# extruder-flex-heater.net
KiCad netlist of a schematic drawn in EAGLE
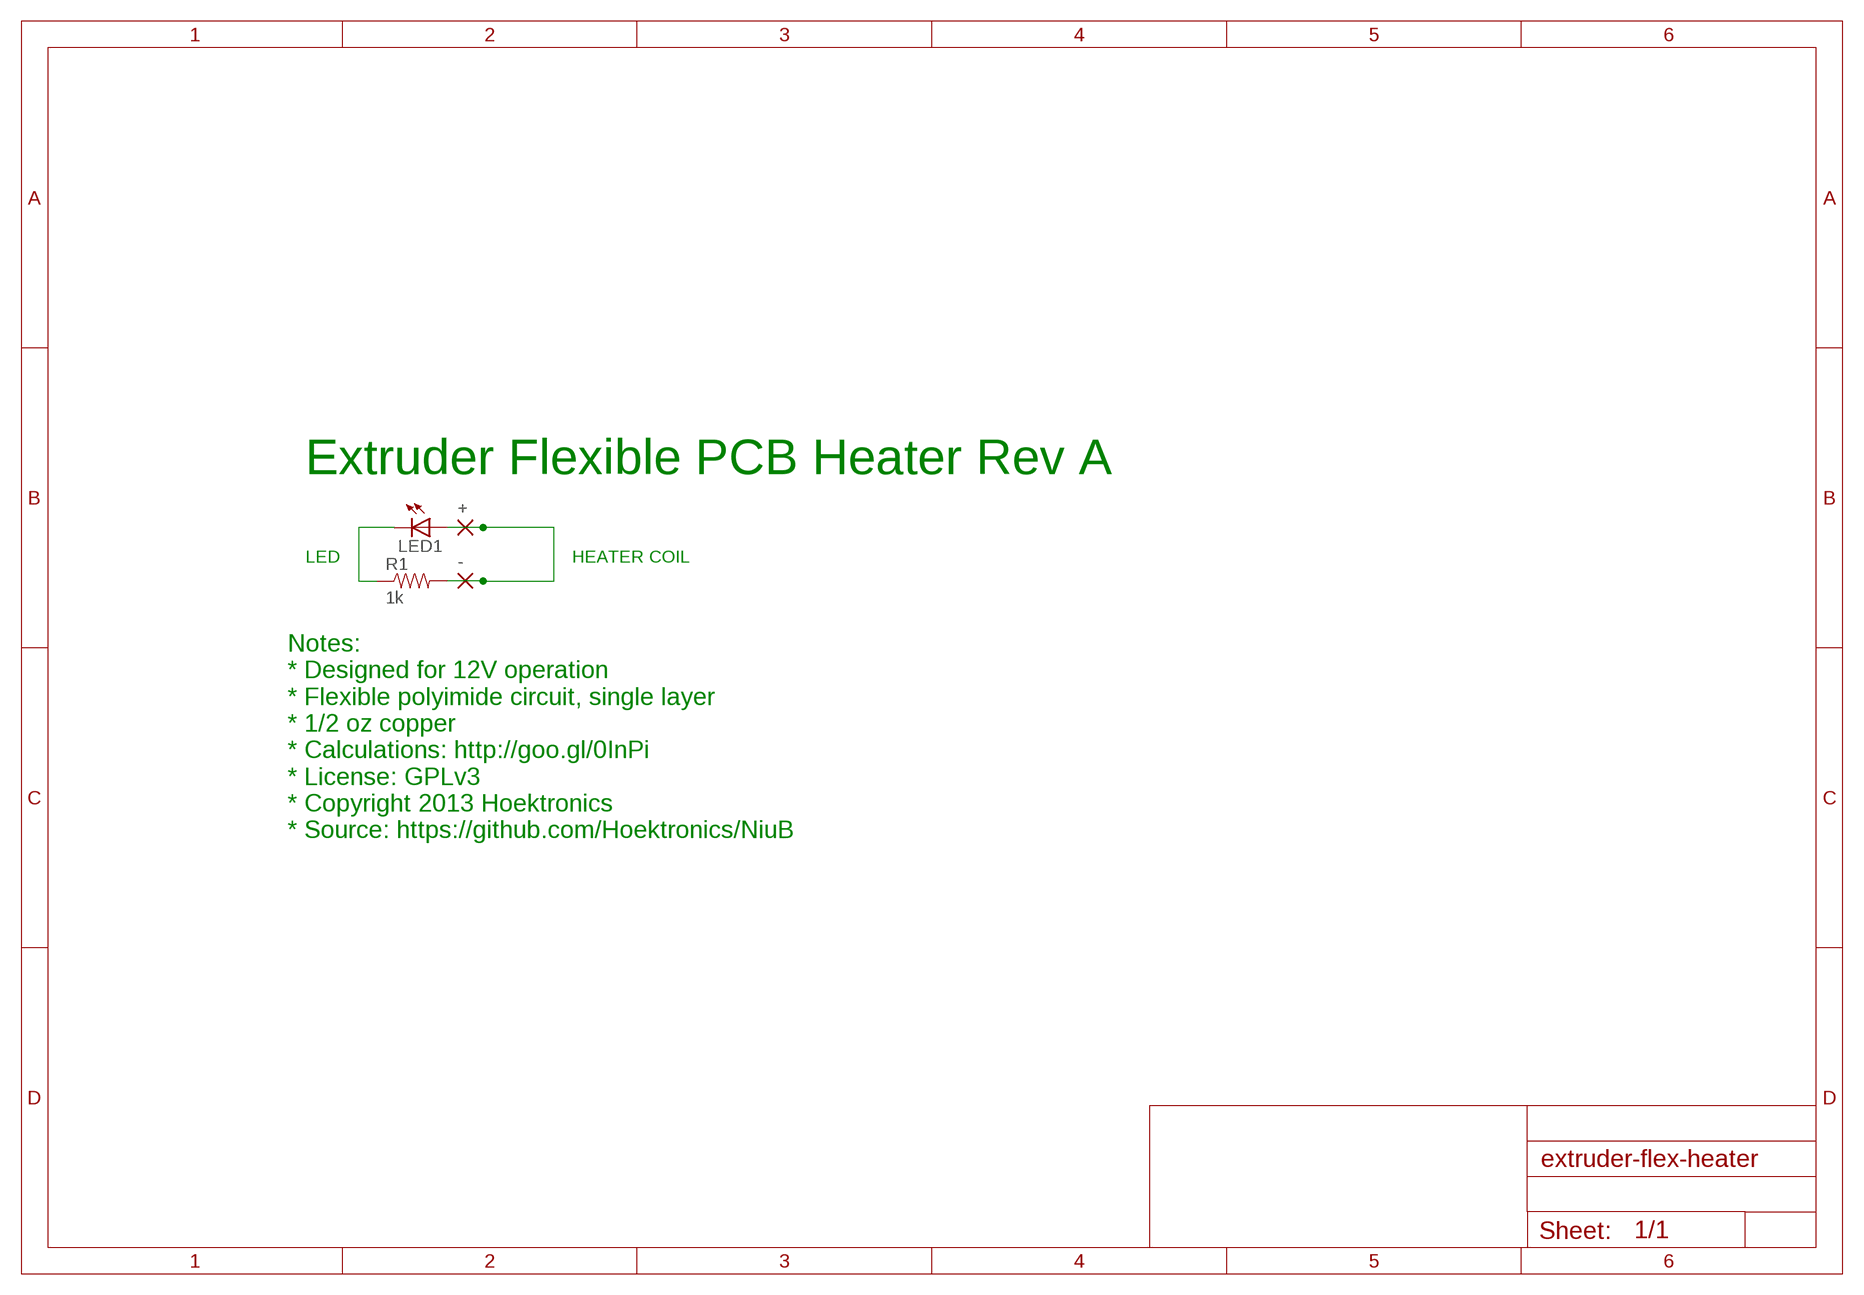
[diagram p0: schematic, sheet 1]

(export (version "E")
  (design (tool "Eeschema 10.0.6"))
  (components
    (comp (ref "+")
      (value "SMD2")
      (footprint "eagle-import:SMD1,27-2,54")
      (libsource (lib "eagle-import") (part "SMD2"))
    )
    (comp (ref "-")
      (value "SMD2")
      (footprint "eagle-import:SMD1,27-2,54")
      (libsource (lib "eagle-import") (part "SMD2"))
    )
    (comp (ref "LED1")
      (value "LED0805")
      (footprint "eagle-import:0805-LED")
      (libsource (lib "eagle-import") (part "LED0805"))
    )
    (comp (ref "R1")
      (value "1k")
      (footprint "eagle-import:0805-RC")
      (libsource (lib "eagle-import") (part "RESISTOR0805"))
    )
  )
  (nets
    (net (code "1") (name "Net-(+-P)") (class "Default")
      (node (ref "+") (pin "1") (pinfunction "P_1") (pintype "passive"))
      (node (ref "-") (pin "1") (pinfunction "P_1") (pintype "passive"))
      (node (ref "LED1") (pin "A") (pinfunction "A_A") (pintype "passive"))
      (node (ref "R1") (pin "2") (pinfunction "2_2") (pintype "passive"))
    )
    (net (code "2") (name "Net-(LED1-PadC)") (class "Default")
      (node (ref "LED1") (pin "C") (pinfunction "C_C") (pintype "passive"))
      (node (ref "R1") (pin "1") (pinfunction "1_1") (pintype "passive"))
    )
  )
)
